# AFPGA_FMC1_bank0.net
KiCad netlist of a schematic drawn in Altium Designer
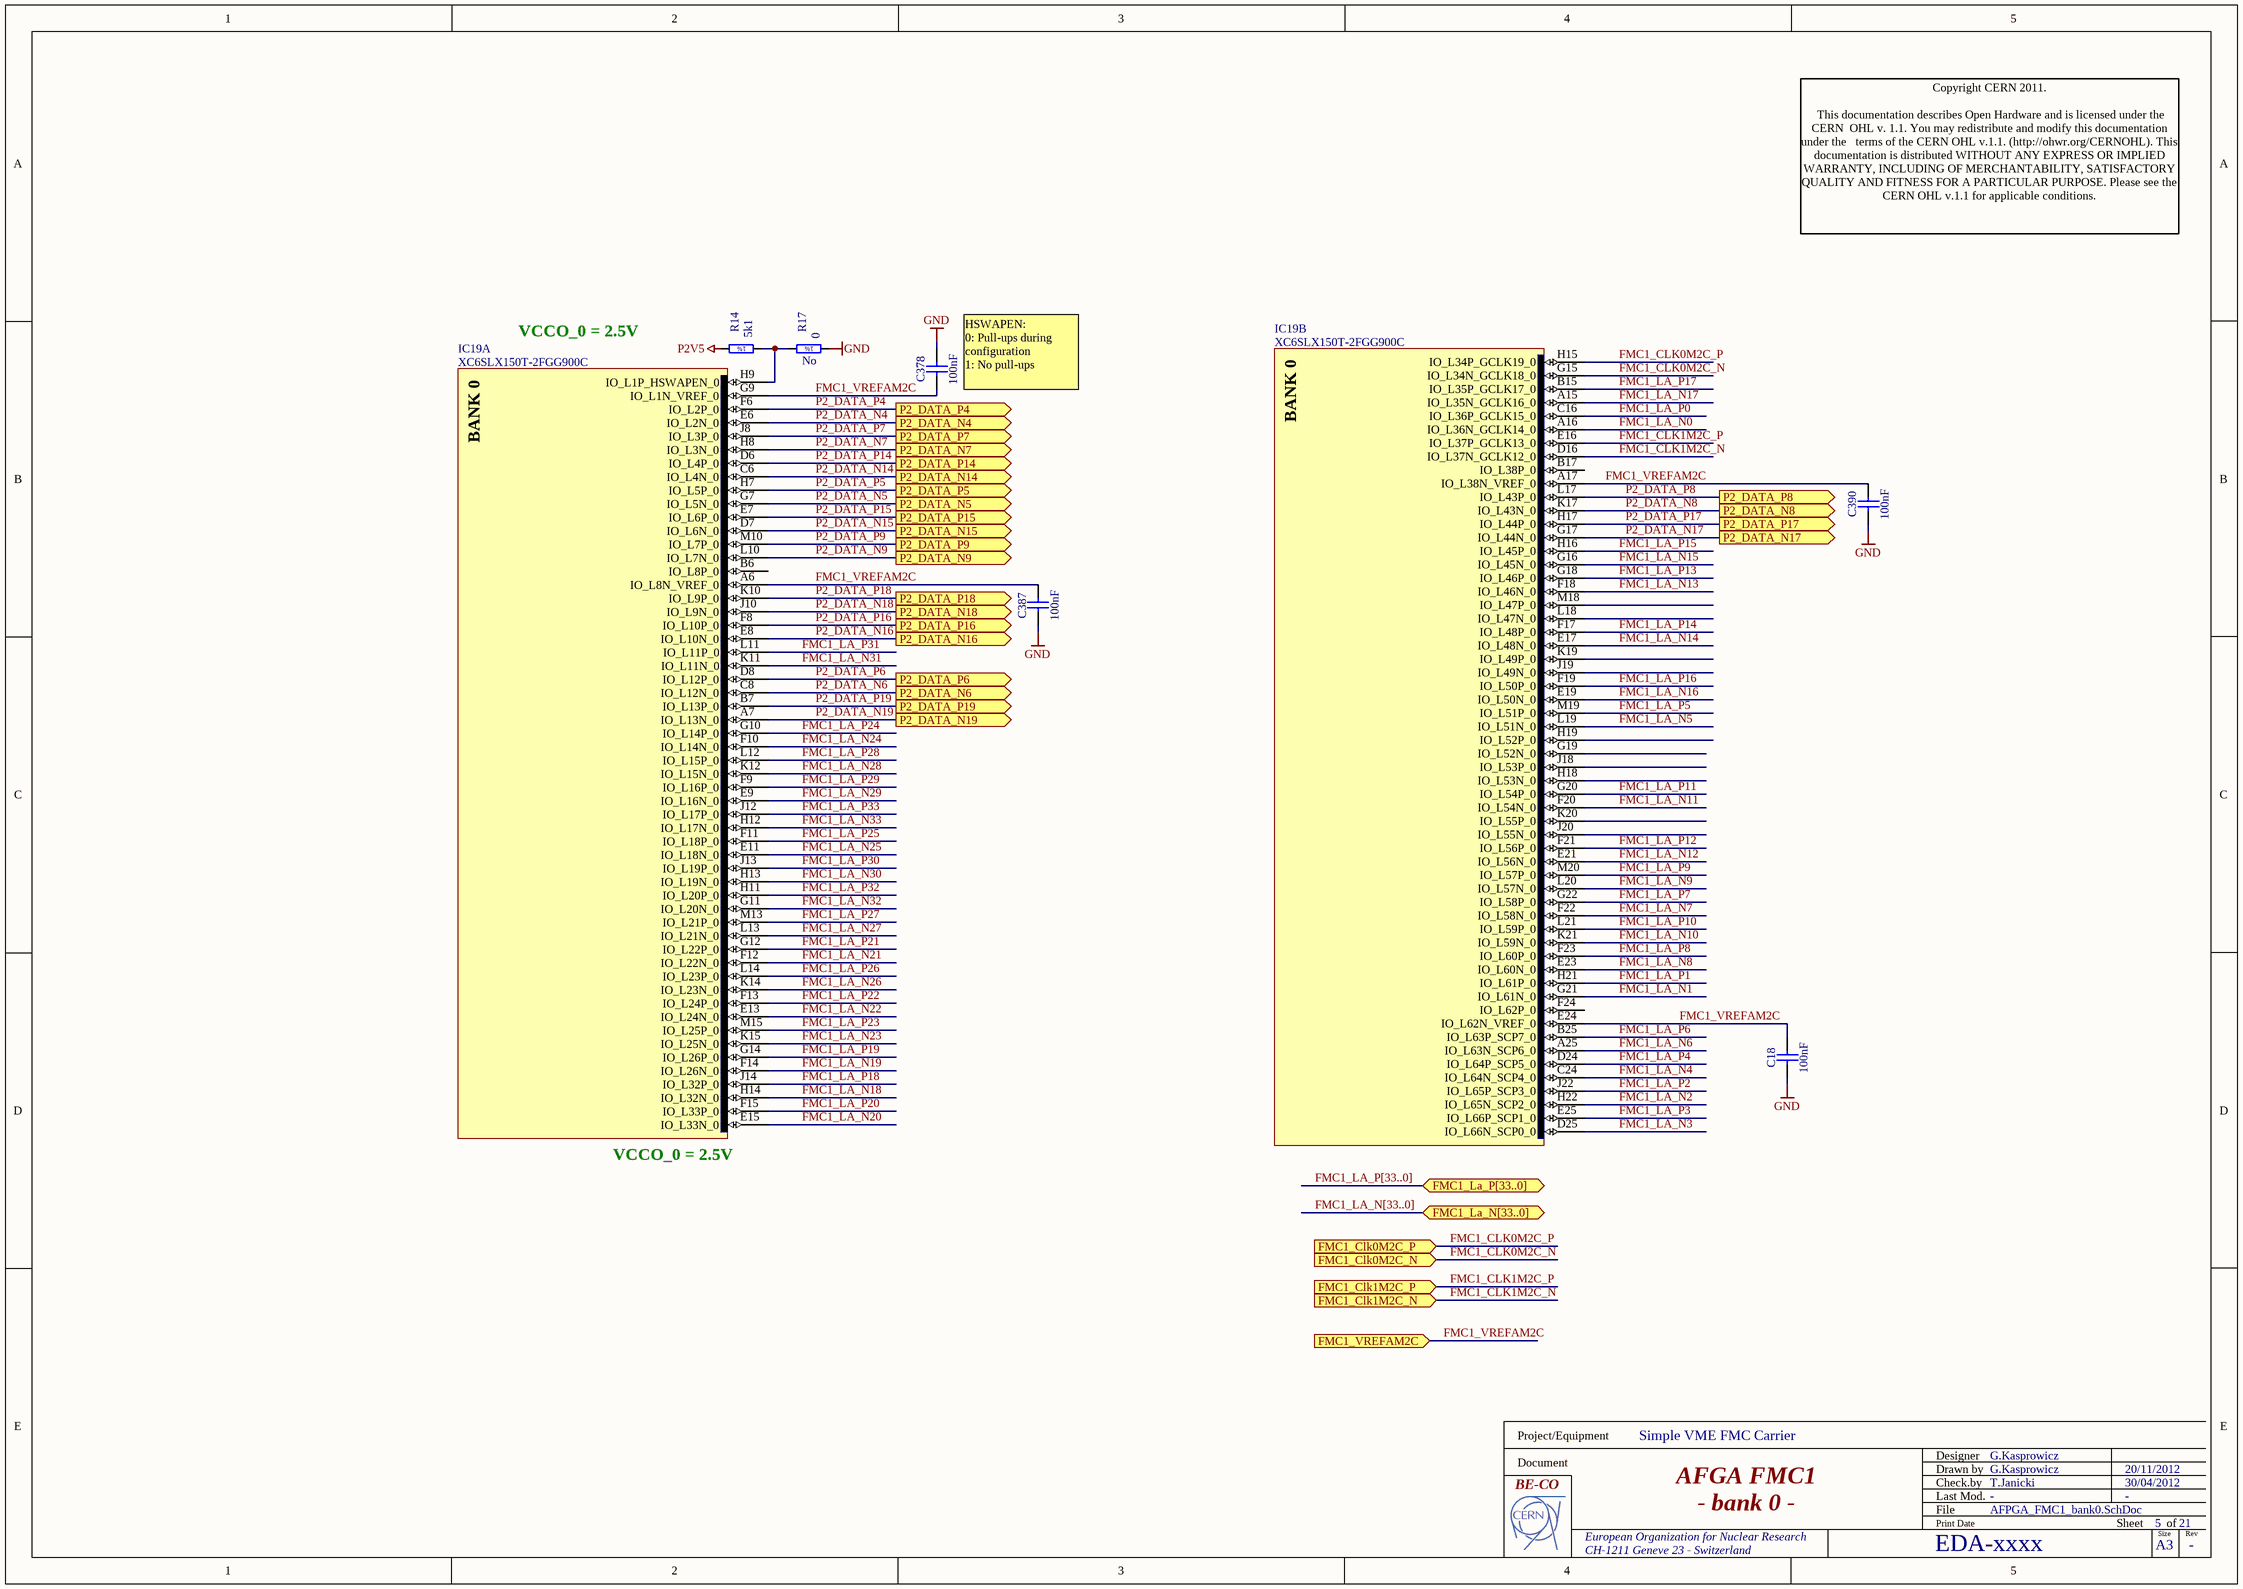
[diagram p0: AFPGA_FMC1_bank0.SchDoc]

(export (version "E")
  (design (tool "Eeschema 10.0.6"))
  (components
    (comp (ref "C18")
      (value "100nF")
      (footprint "CAPC1005X55N")
      (description "Non-polarised capacitor")
      (fields
        (field (name "PART NUMBER") "CC0402_100NF_16V_10%_X7R")
        (field (name "VOLTAGE") "16V")
        (field (name "AUTHOR") "CERN DEM JLC")
      )
      (libsource (lib "Capacitors") (part "Capacitor - non polarized"))
    )
    (comp (ref "C378")
      (value "100nF")
      (footprint "CAPC1005X55N")
      (description "Non-polarised capacitor")
      (fields
        (field (name "PART NUMBER") "CC0402_100NF_16V_10%_X7R")
        (field (name "VOLTAGE") "16V")
        (field (name "AUTHOR") "CERN DEM JLC")
      )
      (libsource (lib "Capacitors") (part "Capacitor - non polarized"))
    )
    (comp (ref "C387")
      (value "100nF")
      (footprint "CAPC1005X55N")
      (description "Non-polarised capacitor")
      (fields
        (field (name "PART NUMBER") "CC0402_100NF_16V_10%_X7R")
        (field (name "VOLTAGE") "16V")
        (field (name "AUTHOR") "CERN DEM JLC")
      )
      (libsource (lib "Capacitors") (part "Capacitor - non polarized"))
    )
    (comp (ref "C390")
      (value "100nF")
      (footprint "CAPC1005X55N")
      (description "Non-polarised capacitor")
      (fields
        (field (name "PART NUMBER") "CC0402_100NF_16V_10%_X7R")
        (field (name "VOLTAGE") "16V")
        (field (name "AUTHOR") "CERN DEM JLC")
      )
      (libsource (lib "Capacitors") (part "Capacitor - non polarized"))
    )
    (comp (ref "IC19")
      (value "XC6SLX150T-2FGG900C")
      (footprint "BGA900C100P30X30_3100X3100X260")
      (description "SPARTAN-6, FPGA, 900-Ball BGA, Commercial Grade, Pb-Free")
      (fields (field (name "MANUFACTURER") "XILINX") (field (name "AUTHOR") "CERN DEM JLC"))
      (libsource (lib "ICs And Semiconductors") (part "XC6SLX150T-2FGG900C"))
    )
    (comp (ref "R14")
      (value "5k1")
      (footprint "RESC1608X55N")
      (description "Resistor - 1%")
      (fields
        (field (name "PART NUMBER") "R0603_5K1_1%_0.1W_100PPM")
        (field (name "POWER") "0.1W")
        (field (name "AUTHOR") "CERN DEM JLC")
      )
      (libsource (lib "Resistors") (part "Resistor - 1%"))
    )
    (comp (ref "R17")
      (value "0")
      (footprint "RESC1608X55N")
      (description "Resistor - 1%")
      (fields
        (field (name "PART NUMBER") "R0603_0R_JUMPER")
        (field (name "MANUFACTURER") "GENERIC")
        (field (name "MOUNTED") "No")
        (field (name "AUTHOR") "CERN DEM JLC")
      )
      (libsource (lib "Resistors") (part "Resistor - 1%"))
    )
  )
  (nets
    (net (code "1") (name "/FMC1_CLK0M2C_N") (class "Default")
      (node (ref "IC19") (pin "G15") (pinfunction "IO_L34N_GCLK18_0_G15") (pintype "bidirectional"))
    )
    (net (code "2") (name "/FMC1_CLK0M2C_P") (class "Default")
      (node (ref "IC19") (pin "H15") (pinfunction "IO_L34P_GCLK19_0_H15") (pintype "bidirectional"))
    )
    (net (code "3") (name "/FMC1_CLK1M2C_N") (class "Default")
      (node (ref "IC19") (pin "D16") (pinfunction "IO_L37N_GCLK12_0_D16") (pintype "bidirectional"))
    )
    (net (code "4") (name "/FMC1_CLK1M2C_P") (class "Default")
      (node (ref "IC19") (pin "E16") (pinfunction "IO_L37P_GCLK13_0_E16") (pintype "bidirectional"))
    )
    (net (code "5") (name "/FMC1_LA_N0") (class "Default")
      (node (ref "IC19") (pin "A16") (pinfunction "IO_L36N_GCLK14_0_A16") (pintype "bidirectional"))
    )
    (net (code "6") (name "/FMC1_LA_N1") (class "Default")
      (node (ref "IC19") (pin "G21") (pinfunction "IO_L61N_0_G21") (pintype "bidirectional"))
    )
    (net (code "7") (name "/FMC1_LA_N2") (class "Default")
      (node (ref "IC19") (pin "H22") (pinfunction "IO_L65N_SCP2_0_H22") (pintype "bidirectional"))
    )
    (net (code "8") (name "/FMC1_LA_N3") (class "Default")
      (node (ref "IC19") (pin "D25") (pinfunction "IO_L66N_SCP0_0_D25") (pintype "bidirectional"))
    )
    (net (code "9") (name "/FMC1_LA_N4") (class "Default")
      (node (ref "IC19") (pin "C24") (pinfunction "IO_L64N_SCP4_0_C24") (pintype "bidirectional"))
    )
    (net (code "10") (name "/FMC1_LA_N5") (class "Default")
      (node (ref "IC19") (pin "L19") (pinfunction "IO_L51N_0_L19") (pintype "bidirectional"))
    )
    (net (code "11") (name "/FMC1_LA_N6") (class "Default")
      (node (ref "IC19") (pin "A25") (pinfunction "IO_L63N_SCP6_0_A25") (pintype "bidirectional"))
    )
    (net (code "12") (name "/FMC1_LA_N7") (class "Default")
      (node (ref "IC19") (pin "F22") (pinfunction "IO_L58N_0_F22") (pintype "bidirectional"))
    )
    (net (code "13") (name "/FMC1_LA_N8") (class "Default")
      (node (ref "IC19") (pin "E23") (pinfunction "IO_L60N_0_E23") (pintype "bidirectional"))
    )
    (net (code "14") (name "/FMC1_LA_N9") (class "Default")
      (node (ref "IC19") (pin "L20") (pinfunction "IO_L57N_0_L20") (pintype "bidirectional"))
    )
    (net (code "15") (name "/FMC1_LA_N10") (class "Default")
      (node (ref "IC19") (pin "K21") (pinfunction "IO_L59N_0_K21") (pintype "bidirectional"))
    )
    (net (code "16") (name "/FMC1_LA_N11") (class "Default")
      (node (ref "IC19") (pin "F20") (pinfunction "IO_L54N_0_F20") (pintype "bidirectional"))
    )
    (net (code "17") (name "/FMC1_LA_N12") (class "Default")
      (node (ref "IC19") (pin "E21") (pinfunction "IO_L56N_0_E21") (pintype "bidirectional"))
    )
    (net (code "18") (name "/FMC1_LA_N13") (class "Default")
      (node (ref "IC19") (pin "F18") (pinfunction "IO_L46N_0_F18") (pintype "bidirectional"))
    )
    (net (code "19") (name "/FMC1_LA_N14") (class "Default")
      (node (ref "IC19") (pin "E17") (pinfunction "IO_L48N_0_E17") (pintype "bidirectional"))
    )
    (net (code "20") (name "/FMC1_LA_N15") (class "Default")
      (node (ref "IC19") (pin "G16") (pinfunction "IO_L45N_0_G16") (pintype "bidirectional"))
    )
    (net (code "21") (name "/FMC1_LA_N16") (class "Default")
      (node (ref "IC19") (pin "E19") (pinfunction "IO_L50N_0_E19") (pintype "bidirectional"))
    )
    (net (code "22") (name "/FMC1_LA_N17") (class "Default")
      (node (ref "IC19") (pin "A15") (pinfunction "IO_L35N_GCLK16_0_A15") (pintype "bidirectional"))
    )
    (net (code "23") (name "/FMC1_LA_N18") (class "Default")
      (node (ref "IC19") (pin "H14") (pinfunction "IO_L32N_0_H14") (pintype "bidirectional"))
    )
    (net (code "24") (name "/FMC1_LA_N19") (class "Default")
      (node (ref "IC19") (pin "F14") (pinfunction "IO_L26N_0_F14") (pintype "bidirectional"))
    )
    (net (code "25") (name "/FMC1_LA_N20") (class "Default")
      (node (ref "IC19") (pin "E15") (pinfunction "IO_L33N_0_E15") (pintype "bidirectional"))
    )
    (net (code "26") (name "/FMC1_LA_N21") (class "Default")
      (node (ref "IC19") (pin "F12") (pinfunction "IO_L22N_0_F12") (pintype "bidirectional"))
    )
    (net (code "27") (name "/FMC1_LA_N22") (class "Default")
      (node (ref "IC19") (pin "E13") (pinfunction "IO_L24N_0_E13") (pintype "bidirectional"))
    )
    (net (code "28") (name "/FMC1_LA_N23") (class "Default")
      (node (ref "IC19") (pin "K15") (pinfunction "IO_L25N_0_K15") (pintype "bidirectional"))
    )
    (net (code "29") (name "/FMC1_LA_N24") (class "Default")
      (node (ref "IC19") (pin "F10") (pinfunction "IO_L14N_0_F10") (pintype "bidirectional"))
    )
    (net (code "30") (name "/FMC1_LA_N25") (class "Default")
      (node (ref "IC19") (pin "E11") (pinfunction "IO_L18N_0_E11") (pintype "bidirectional"))
    )
    (net (code "31") (name "/FMC1_LA_N26") (class "Default")
      (node (ref "IC19") (pin "K14") (pinfunction "IO_L23N_0_K14") (pintype "bidirectional"))
    )
    (net (code "32") (name "/FMC1_LA_N27") (class "Default")
      (node (ref "IC19") (pin "L13") (pinfunction "IO_L21N_0_L13") (pintype "bidirectional"))
    )
    (net (code "33") (name "/FMC1_LA_N28") (class "Default")
      (node (ref "IC19") (pin "K12") (pinfunction "IO_L15N_0_K12") (pintype "bidirectional"))
    )
    (net (code "34") (name "/FMC1_LA_N29") (class "Default")
      (node (ref "IC19") (pin "E9") (pinfunction "IO_L16N_0_E9") (pintype "bidirectional"))
    )
    (net (code "35") (name "/FMC1_LA_N30") (class "Default")
      (node (ref "IC19") (pin "H13") (pinfunction "IO_L19N_0_H13") (pintype "bidirectional"))
    )
    (net (code "36") (name "/FMC1_LA_N31") (class "Default")
      (node (ref "IC19") (pin "K11") (pinfunction "IO_L11N_0_K11") (pintype "bidirectional"))
    )
    (net (code "37") (name "/FMC1_LA_N32") (class "Default")
      (node (ref "IC19") (pin "G11") (pinfunction "IO_L20N_0_G11") (pintype "bidirectional"))
    )
    (net (code "38") (name "/FMC1_LA_N33") (class "Default")
      (node (ref "IC19") (pin "H12") (pinfunction "IO_L17N_0_H12") (pintype "bidirectional"))
    )
    (net (code "40") (name "/FMC1_LA_P0") (class "Default")
      (node (ref "IC19") (pin "C16") (pinfunction "IO_L36P_GCLK15_0_C16") (pintype "bidirectional"))
    )
    (net (code "41") (name "/FMC1_LA_P1") (class "Default")
      (node (ref "IC19") (pin "H21") (pinfunction "IO_L61P_0_H21") (pintype "bidirectional"))
    )
    (net (code "42") (name "/FMC1_LA_P2") (class "Default")
      (node (ref "IC19") (pin "J22") (pinfunction "IO_L65P_SCP3_0_J22") (pintype "bidirectional"))
    )
    (net (code "43") (name "/FMC1_LA_P3") (class "Default")
      (node (ref "IC19") (pin "E25") (pinfunction "IO_L66P_SCP1_0_E25") (pintype "bidirectional"))
    )
    (net (code "44") (name "/FMC1_LA_P4") (class "Default")
      (node (ref "IC19") (pin "D24") (pinfunction "IO_L64P_SCP5_0_D24") (pintype "bidirectional"))
    )
    (net (code "45") (name "/FMC1_LA_P5") (class "Default")
      (node (ref "IC19") (pin "M19") (pinfunction "IO_L51P_0_M19") (pintype "bidirectional"))
    )
    (net (code "46") (name "/FMC1_LA_P6") (class "Default")
      (node (ref "IC19") (pin "B25") (pinfunction "IO_L63P_SCP7_0_B25") (pintype "bidirectional"))
    )
    (net (code "47") (name "/FMC1_LA_P7") (class "Default")
      (node (ref "IC19") (pin "G22") (pinfunction "IO_L58P_0_G22") (pintype "bidirectional"))
    )
    (net (code "48") (name "/FMC1_LA_P8") (class "Default")
      (node (ref "IC19") (pin "F23") (pinfunction "IO_L60P_0_F23") (pintype "bidirectional"))
    )
    (net (code "49") (name "/FMC1_LA_P9") (class "Default")
      (node (ref "IC19") (pin "M20") (pinfunction "IO_L57P_0_M20") (pintype "bidirectional"))
    )
    (net (code "50") (name "/FMC1_LA_P10") (class "Default")
      (node (ref "IC19") (pin "L21") (pinfunction "IO_L59P_0_L21") (pintype "bidirectional"))
    )
    (net (code "51") (name "/FMC1_LA_P11") (class "Default")
      (node (ref "IC19") (pin "G20") (pinfunction "IO_L54P_0_G20") (pintype "bidirectional"))
    )
    (net (code "52") (name "/FMC1_LA_P12") (class "Default")
      (node (ref "IC19") (pin "F21") (pinfunction "IO_L56P_0_F21") (pintype "bidirectional"))
    )
    (net (code "53") (name "/FMC1_LA_P13") (class "Default")
      (node (ref "IC19") (pin "G18") (pinfunction "IO_L46P_0_G18") (pintype "bidirectional"))
    )
    (net (code "54") (name "/FMC1_LA_P14") (class "Default")
      (node (ref "IC19") (pin "F17") (pinfunction "IO_L48P_0_F17") (pintype "bidirectional"))
    )
    (net (code "55") (name "/FMC1_LA_P15") (class "Default")
      (node (ref "IC19") (pin "H16") (pinfunction "IO_L45P_0_H16") (pintype "bidirectional"))
    )
    (net (code "56") (name "/FMC1_LA_P16") (class "Default")
      (node (ref "IC19") (pin "F19") (pinfunction "IO_L50P_0_F19") (pintype "bidirectional"))
    )
    (net (code "57") (name "/FMC1_LA_P17") (class "Default")
      (node (ref "IC19") (pin "B15") (pinfunction "IO_L35P_GCLK17_0_B15") (pintype "bidirectional"))
    )
    (net (code "58") (name "/FMC1_LA_P18") (class "Default")
      (node (ref "IC19") (pin "J14") (pinfunction "IO_L32P_0_J14") (pintype "bidirectional"))
    )
    (net (code "59") (name "/FMC1_LA_P19") (class "Default")
      (node (ref "IC19") (pin "G14") (pinfunction "IO_L26P_0_G14") (pintype "bidirectional"))
    )
    (net (code "60") (name "/FMC1_LA_P20") (class "Default")
      (node (ref "IC19") (pin "F15") (pinfunction "IO_L33P_0_F15") (pintype "bidirectional"))
    )
    (net (code "61") (name "/FMC1_LA_P21") (class "Default")
      (node (ref "IC19") (pin "G12") (pinfunction "IO_L22P_0_G12") (pintype "bidirectional"))
    )
    (net (code "62") (name "/FMC1_LA_P22") (class "Default")
      (node (ref "IC19") (pin "F13") (pinfunction "IO_L24P_0_F13") (pintype "bidirectional"))
    )
    (net (code "63") (name "/FMC1_LA_P23") (class "Default")
      (node (ref "IC19") (pin "M15") (pinfunction "IO_L25P_0_M15") (pintype "bidirectional"))
    )
    (net (code "64") (name "/FMC1_LA_P24") (class "Default")
      (node (ref "IC19") (pin "G10") (pinfunction "IO_L14P_0_G10") (pintype "bidirectional"))
    )
    (net (code "65") (name "/FMC1_LA_P25") (class "Default")
      (node (ref "IC19") (pin "F11") (pinfunction "IO_L18P_0_F11") (pintype "bidirectional"))
    )
    (net (code "66") (name "/FMC1_LA_P26") (class "Default")
      (node (ref "IC19") (pin "L14") (pinfunction "IO_L23P_0_L14") (pintype "bidirectional"))
    )
    (net (code "67") (name "/FMC1_LA_P27") (class "Default")
      (node (ref "IC19") (pin "M13") (pinfunction "IO_L21P_0_M13") (pintype "bidirectional"))
    )
    (net (code "68") (name "/FMC1_LA_P28") (class "Default")
      (node (ref "IC19") (pin "L12") (pinfunction "IO_L15P_0_L12") (pintype "bidirectional"))
    )
    (net (code "69") (name "/FMC1_LA_P29") (class "Default")
      (node (ref "IC19") (pin "F9") (pinfunction "IO_L16P_0_F9") (pintype "bidirectional"))
    )
    (net (code "70") (name "/FMC1_LA_P30") (class "Default")
      (node (ref "IC19") (pin "J13") (pinfunction "IO_L19P_0_J13") (pintype "bidirectional"))
    )
    (net (code "71") (name "/FMC1_LA_P31") (class "Default")
      (node (ref "IC19") (pin "L11") (pinfunction "IO_L11P_0_L11") (pintype "bidirectional"))
    )
    (net (code "72") (name "/FMC1_LA_P32") (class "Default")
      (node (ref "IC19") (pin "H11") (pinfunction "IO_L20P_0_H11") (pintype "bidirectional"))
    )
    (net (code "73") (name "/FMC1_LA_P33") (class "Default")
      (node (ref "IC19") (pin "J12") (pinfunction "IO_L17P_0_J12") (pintype "bidirectional"))
    )
    (net (code "75") (name "/FMC1_VREFAM2C") (class "Default")
      (node (ref "C18") (pin "2") (pinfunction "2_2") (pintype "passive"))
      (node (ref "C378") (pin "1") (pinfunction "1_1") (pintype "passive"))
      (node (ref "C387") (pin "2") (pinfunction "2_2") (pintype "passive"))
      (node (ref "C390") (pin "2") (pinfunction "2_2") (pintype "passive"))
      (node (ref "IC19") (pin "A17") (pinfunction "IO_L38N_VREF_0_A17") (pintype "bidirectional"))
      (node (ref "IC19") (pin "A6") (pinfunction "IO_L8N_VREF_0_A6") (pintype "bidirectional"))
      (node (ref "IC19") (pin "E24") (pinfunction "IO_L62N_VREF_0_E24") (pintype "bidirectional"))
      (node (ref "IC19") (pin "G9") (pinfunction "IO_L1N_VREF_0_G9") (pintype "bidirectional"))
    )
    (net (code "76") (name "/P2_DATA_N4") (class "Default")
      (node (ref "IC19") (pin "E6") (pinfunction "IO_L2N_0_E6") (pintype "bidirectional"))
    )
    (net (code "77") (name "/P2_DATA_N5") (class "Default")
      (node (ref "IC19") (pin "G7") (pinfunction "IO_L5N_0_G7") (pintype "bidirectional"))
    )
    (net (code "78") (name "/P2_DATA_N6") (class "Default")
      (node (ref "IC19") (pin "C8") (pinfunction "IO_L12N_0_C8") (pintype "bidirectional"))
    )
    (net (code "79") (name "/P2_DATA_N7") (class "Default")
      (node (ref "IC19") (pin "H8") (pinfunction "IO_L3N_0_H8") (pintype "bidirectional"))
    )
    (net (code "80") (name "/P2_DATA_N8") (class "Default")
      (node (ref "IC19") (pin "K17") (pinfunction "IO_L43N_0_K17") (pintype "bidirectional"))
    )
    (net (code "81") (name "/P2_DATA_N9") (class "Default")
      (node (ref "IC19") (pin "L10") (pinfunction "IO_L7N_0_L10") (pintype "bidirectional"))
    )
    (net (code "82") (name "/P2_DATA_N14") (class "Default")
      (node (ref "IC19") (pin "C6") (pinfunction "IO_L4N_0_C6") (pintype "bidirectional"))
    )
    (net (code "83") (name "/P2_DATA_N15") (class "Default")
      (node (ref "IC19") (pin "D7") (pinfunction "IO_L6N_0_D7") (pintype "bidirectional"))
    )
    (net (code "84") (name "/P2_DATA_N16") (class "Default")
      (node (ref "IC19") (pin "E8") (pinfunction "IO_L10N_0_E8") (pintype "bidirectional"))
    )
    (net (code "85") (name "/P2_DATA_N17") (class "Default")
      (node (ref "IC19") (pin "G17") (pinfunction "IO_L44N_0_G17") (pintype "bidirectional"))
    )
    (net (code "86") (name "/P2_DATA_N18") (class "Default")
      (node (ref "IC19") (pin "J10") (pinfunction "IO_L9N_0_J10") (pintype "bidirectional"))
    )
    (net (code "87") (name "/P2_DATA_N19") (class "Default")
      (node (ref "IC19") (pin "A7") (pinfunction "IO_L13N_0_A7") (pintype "bidirectional"))
    )
    (net (code "88") (name "/P2_DATA_P4") (class "Default")
      (node (ref "IC19") (pin "F6") (pinfunction "IO_L2P_0_F6") (pintype "bidirectional"))
    )
    (net (code "89") (name "/P2_DATA_P5") (class "Default")
      (node (ref "IC19") (pin "H7") (pinfunction "IO_L5P_0_H7") (pintype "bidirectional"))
    )
    (net (code "90") (name "/P2_DATA_P6") (class "Default")
      (node (ref "IC19") (pin "D8") (pinfunction "IO_L12P_0_D8") (pintype "bidirectional"))
    )
    (net (code "91") (name "/P2_DATA_P7") (class "Default")
      (node (ref "IC19") (pin "J8") (pinfunction "IO_L3P_0_J8") (pintype "bidirectional"))
    )
    (net (code "92") (name "/P2_DATA_P8") (class "Default")
      (node (ref "IC19") (pin "L17") (pinfunction "IO_L43P_0_L17") (pintype "bidirectional"))
    )
    (net (code "93") (name "/P2_DATA_P9") (class "Default")
      (node (ref "IC19") (pin "M10") (pinfunction "IO_L7P_0_M10") (pintype "bidirectional"))
    )
    (net (code "94") (name "/P2_DATA_P14") (class "Default")
      (node (ref "IC19") (pin "D6") (pinfunction "IO_L4P_0_D6") (pintype "bidirectional"))
    )
    (net (code "95") (name "/P2_DATA_P15") (class "Default")
      (node (ref "IC19") (pin "E7") (pinfunction "IO_L6P_0_E7") (pintype "bidirectional"))
    )
    (net (code "96") (name "/P2_DATA_P16") (class "Default")
      (node (ref "IC19") (pin "F8") (pinfunction "IO_L10P_0_F8") (pintype "bidirectional"))
    )
    (net (code "97") (name "/P2_DATA_P17") (class "Default")
      (node (ref "IC19") (pin "H17") (pinfunction "IO_L44P_0_H17") (pintype "bidirectional"))
    )
    (net (code "98") (name "/P2_DATA_P18") (class "Default")
      (node (ref "IC19") (pin "K10") (pinfunction "IO_L9P_0_K10") (pintype "bidirectional"))
    )
    (net (code "99") (name "/P2_DATA_P19") (class "Default")
      (node (ref "IC19") (pin "B7") (pinfunction "IO_L13P_0_B7") (pintype "bidirectional"))
    )
    (net (code "100") (name "GND") (class "Default")
      (node (ref "C18") (pin "1") (pinfunction "1_1") (pintype "passive"))
      (node (ref "C378") (pin "2") (pinfunction "2_2") (pintype "passive"))
      (node (ref "C387") (pin "1") (pinfunction "1_1") (pintype "passive"))
      (node (ref "C390") (pin "1") (pinfunction "1_1") (pintype "passive"))
      (node (ref "R17") (pin "1") (pinfunction "1_1") (pintype "passive"))
    )
    (net (code "101") (name "Net-(IC19A-IO_L1P_HSWAPEN_0)") (class "Default")
      (node (ref "IC19") (pin "H9") (pinfunction "IO_L1P_HSWAPEN_0_H9") (pintype "bidirectional"))
      (node (ref "R14") (pin "1") (pinfunction "1_1") (pintype "passive"))
      (node (ref "R17") (pin "2") (pinfunction "2_2") (pintype "passive"))
    )
    (net (code "102") (name "P2V5") (class "Default")
      (node (ref "R14") (pin "2") (pinfunction "2_2") (pintype "passive"))
    )
    (net (code "103") (name "unconnected-(IC19A-IO_L8P_0-PadB6)") (class "Default")
      (node (ref "IC19") (pin "B6") (pinfunction "IO_L8P_0_B6") (pintype "bidirectional"))
    )
    (net (code "104") (name "unconnected-(IC19B-IO_L38P_0-PadB17)") (class "Default")
      (node (ref "IC19") (pin "B17") (pinfunction "IO_L38P_0_B17") (pintype "bidirectional"))
    )
    (net (code "105") (name "unconnected-(IC19B-IO_L47N_0-PadL18)") (class "Default")
      (node (ref "IC19") (pin "L18") (pinfunction "IO_L47N_0_L18") (pintype "bidirectional"))
    )
    (net (code "106") (name "unconnected-(IC19B-IO_L47P_0-PadM18)") (class "Default")
      (node (ref "IC19") (pin "M18") (pinfunction "IO_L47P_0_M18") (pintype "bidirectional"))
    )
    (net (code "107") (name "unconnected-(IC19B-IO_L49N_0-PadJ19)") (class "Default")
      (node (ref "IC19") (pin "J19") (pinfunction "IO_L49N_0_J19") (pintype "bidirectional"))
    )
    (net (code "108") (name "unconnected-(IC19B-IO_L49P_0-PadK19)") (class "Default")
      (node (ref "IC19") (pin "K19") (pinfunction "IO_L49P_0_K19") (pintype "bidirectional"))
    )
    (net (code "109") (name "unconnected-(IC19B-IO_L52N_0-PadG19)") (class "Default")
      (node (ref "IC19") (pin "G19") (pinfunction "IO_L52N_0_G19") (pintype "bidirectional"))
    )
    (net (code "110") (name "unconnected-(IC19B-IO_L52P_0-PadH19)") (class "Default")
      (node (ref "IC19") (pin "H19") (pinfunction "IO_L52P_0_H19") (pintype "bidirectional"))
    )
    (net (code "111") (name "unconnected-(IC19B-IO_L53N_0-PadH18)") (class "Default")
      (node (ref "IC19") (pin "H18") (pinfunction "IO_L53N_0_H18") (pintype "bidirectional"))
    )
    (net (code "112") (name "unconnected-(IC19B-IO_L53P_0-PadJ18)") (class "Default")
      (node (ref "IC19") (pin "J18") (pinfunction "IO_L53P_0_J18") (pintype "bidirectional"))
    )
    (net (code "113") (name "unconnected-(IC19B-IO_L55N_0-PadJ20)") (class "Default")
      (node (ref "IC19") (pin "J20") (pinfunction "IO_L55N_0_J20") (pintype "bidirectional"))
    )
    (net (code "114") (name "unconnected-(IC19B-IO_L55P_0-PadK20)") (class "Default")
      (node (ref "IC19") (pin "K20") (pinfunction "IO_L55P_0_K20") (pintype "bidirectional"))
    )
    (net (code "115") (name "unconnected-(IC19B-IO_L62P_0-PadF24)") (class "Default")
      (node (ref "IC19") (pin "F24") (pinfunction "IO_L62P_0_F24") (pintype "bidirectional"))
    )
  )
)
